# CW340_SPI_flashes.net
KiCad netlist of a schematic drawn in Altium Designer
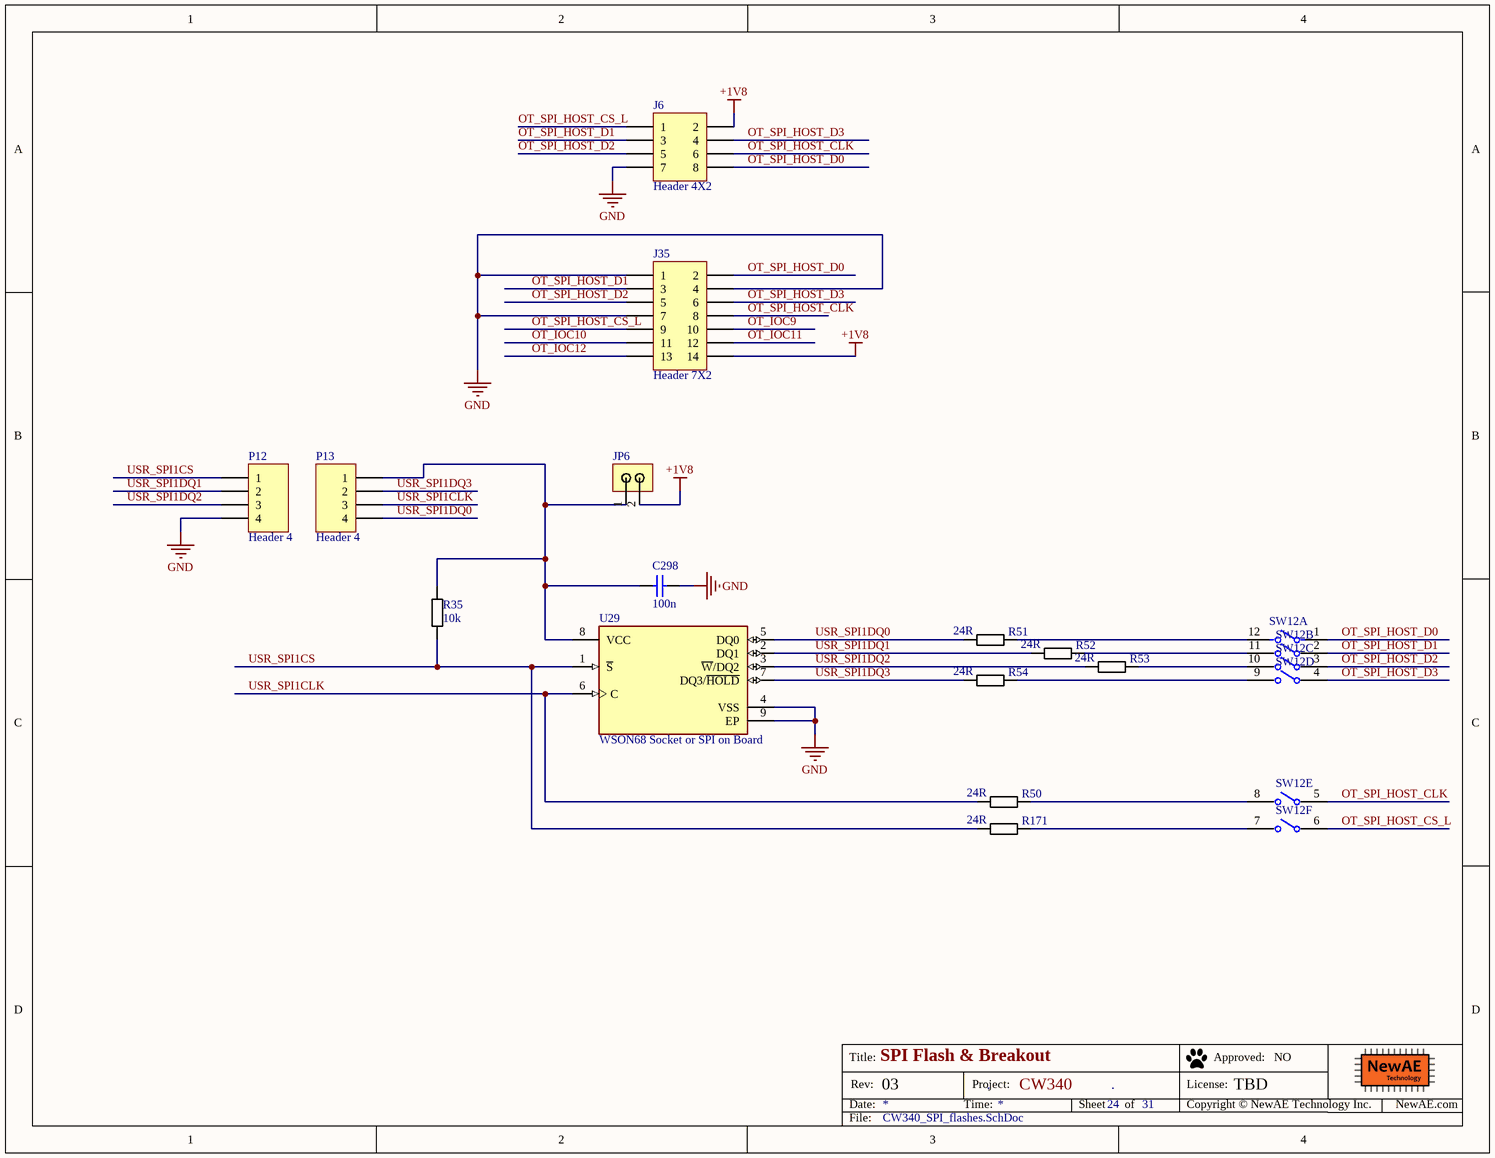
[diagram p0: CW340_SPI_flashes.SchDoc]

(export (version "E")
  (design (tool "Eeschema 10.0.6"))
  (components
    (comp (ref "C298")
      (value "100n")
      (footprint "CAPC0402_M")
      (description "100n, 0402")
      (fields (field (name "PART NUMBER") "CCHIP-100n-0402"))
      (libsource (lib "NewAE_AltiumLib") (part "CAP"))
    )
    (comp (ref "J6")
      (value "Header 4X2")
      (footprint "HDR2X4")
      (description "Header, 4-Pin, Dual row")
      (fields (field (name "PUBLISHER") "Altium Limited"))
      (libsource (lib "Miscellaneous Connectors") (part "Header 4X2"))
    )
    (comp (ref "J35")
      (value "Header 7X2")
      (footprint "HDR2X7")
      (description "Header, 7-Pin, Dual row")
      (fields (field (name "PUBLISHER") "Altium Limited"))
      (libsource (lib "Miscellaneous Connectors") (part "Header 7X2"))
    )
    (comp (ref "JP6")
      (value "Jumper")
      (footprint "2x2.54mm_Header")
      (description "1x2 2.54mm header, male pins")
      (fields (field (name "PART NUMBER") "2_PIN_JUMPER"))
      (libsource (lib "NewAE_AltiumLib") (part "1x2_Pin_Header"))
    )
    (comp (ref "P12")
      (value "Header 4")
      (footprint "HDR1X4")
      (description "Header, 4-Pin")
      (fields (field (name "PUBLISHER") "Altium Limited"))
      (libsource (lib "") (part "Header 4_1"))
    )
    (comp (ref "P13")
      (value "Header 4")
      (footprint "HDR1X4")
      (description "Header, 4-Pin")
      (fields (field (name "PUBLISHER") "Altium Limited"))
      (libsource (lib "Miscellaneous Connectors") (part "Header 4"))
    )
    (comp (ref "R35")
      (value "10k")
      (footprint "RESC1005X40N")
      (description "10k res, 0402, 1%, 1/16W")
      (fields (field (name "PART NUMBER") "RCHIP-10K-0402") (field (name "TOLERANCE") "1%"))
      (libsource (lib "NewAE_AltiumLib") (part "RES-EU"))
    )
    (comp (ref "R50")
      (value "24R")
      (footprint "RESC1005X40N")
      (description "24R res, 0402, 1%, 1/16W")
      (fields (field (name "PART NUMBER") "RCHIP-24R-0402") (field (name "TOLERANCE") "1%"))
      (libsource (lib "") (part "RES-EU_1"))
    )
    (comp (ref "R51")
      (value "24R")
      (footprint "RESC1005X40N")
      (description "24R res, 0402, 1%, 1/16W")
      (fields (field (name "PART NUMBER") "RCHIP-24R-0402") (field (name "TOLERANCE") "1%"))
      (libsource (lib "") (part "RES-EU_1"))
    )
    (comp (ref "R52")
      (value "24R")
      (footprint "RESC1005X40N")
      (description "24R res, 0402, 1%, 1/16W")
      (fields (field (name "PART NUMBER") "RCHIP-24R-0402") (field (name "TOLERANCE") "1%"))
      (libsource (lib "") (part "RES-EU_1"))
    )
    (comp (ref "R53")
      (value "24R")
      (footprint "RESC1005X40N")
      (description "24R res, 0402, 1%, 1/16W")
      (fields (field (name "PART NUMBER") "RCHIP-24R-0402") (field (name "TOLERANCE") "1%"))
      (libsource (lib "") (part "RES-EU_1"))
    )
    (comp (ref "R54")
      (value "24R")
      (footprint "RESC1005X40N")
      (description "24R res, 0402, 1%, 1/16W")
      (fields (field (name "PART NUMBER") "RCHIP-24R-0402") (field (name "TOLERANCE") "1%"))
      (libsource (lib "") (part "RES-EU_1"))
    )
    (comp (ref "R171")
      (value "24R")
      (footprint "RESC1005X40N")
      (description "24R res, 0402, 1%, 1/16W")
      (fields (field (name "PART NUMBER") "RCHIP-24R-0402") (field (name "TOLERANCE") "1%"))
      (libsource (lib "") (part "RES-EU_1"))
    )
    (comp (ref "SW12")
      (value "A6H-6101-PM")
      (footprint "FP-A6H-6101-PM-MFG")
      (description "6 DIP switch SMD")
      (libsource (lib "NewAE_AltiumLib") (part "A6H-6101-PM"))
    )
    (comp (ref "U29")
      (value "WSON68 Socket or SPI on Board")
      (footprint "SOK-SPI-WSON68_ORCHIP")
      (description "WSON-6x8 Socket OR WSON Flash")
      (fields (field (name "PART NUMBER") "SOK-SPI-WSON68_OR_QSPI"))
      (libsource (lib "NewAE_AltiumLib") (part "QSPI_WSON"))
    )
  )
  (nets
    (net (code "1") (name "+1V8") (class "Default")
      (node (ref "J35") (pin "14") (pinfunction "14_14") (pintype "passive"))
      (node (ref "J6") (pin "2") (pinfunction "2_2") (pintype "passive"))
      (node (ref "JP6") (pin "2") (pinfunction "2_2") (pintype "passive"))
    )
    (net (code "2") (name "/OT_IOC9") (class "Default")
      (node (ref "J35") (pin "10") (pinfunction "10_10") (pintype "passive"))
    )
    (net (code "3") (name "/OT_IOC10") (class "Default")
      (node (ref "J35") (pin "11") (pinfunction "11_11") (pintype "passive"))
    )
    (net (code "4") (name "/OT_IOC11") (class "Default")
      (node (ref "J35") (pin "12") (pinfunction "12_12") (pintype "passive"))
    )
    (net (code "5") (name "/OT_IOC12") (class "Default")
      (node (ref "J35") (pin "13") (pinfunction "13_13") (pintype "passive"))
    )
    (net (code "6") (name "/OT_SPI_HOST_CLK") (class "Default")
      (node (ref "J35") (pin "8") (pinfunction "8_8") (pintype "passive"))
      (node (ref "J6") (pin "6") (pinfunction "6_6") (pintype "passive"))
      (node (ref "SW12") (pin "5") (pinfunction "5_5") (pintype "passive"))
    )
    (net (code "7") (name "/OT_SPI_HOST_CS_L") (class "Default")
      (node (ref "J35") (pin "9") (pinfunction "9_9") (pintype "passive"))
      (node (ref "J6") (pin "1") (pinfunction "1_1") (pintype "passive"))
      (node (ref "SW12") (pin "6") (pinfunction "6_6") (pintype "passive"))
    )
    (net (code "8") (name "/OT_SPI_HOST_D0") (class "Default")
      (node (ref "J35") (pin "2") (pinfunction "2_2") (pintype "passive"))
      (node (ref "J6") (pin "8") (pinfunction "8_8") (pintype "passive"))
      (node (ref "SW12") (pin "1") (pinfunction "1_1") (pintype "passive"))
    )
    (net (code "9") (name "/OT_SPI_HOST_D1") (class "Default")
      (node (ref "J35") (pin "3") (pinfunction "3_3") (pintype "passive"))
      (node (ref "J6") (pin "3") (pinfunction "3_3") (pintype "passive"))
      (node (ref "SW12") (pin "2") (pinfunction "2_2") (pintype "passive"))
    )
    (net (code "10") (name "/OT_SPI_HOST_D2") (class "Default")
      (node (ref "J35") (pin "5") (pinfunction "5_5") (pintype "passive"))
      (node (ref "J6") (pin "5") (pinfunction "5_5") (pintype "passive"))
      (node (ref "SW12") (pin "3") (pinfunction "3_3") (pintype "passive"))
    )
    (net (code "11") (name "/OT_SPI_HOST_D3") (class "Default")
      (node (ref "J35") (pin "6") (pinfunction "6_6") (pintype "passive"))
      (node (ref "J6") (pin "4") (pinfunction "4_4") (pintype "passive"))
      (node (ref "SW12") (pin "4") (pinfunction "4_4") (pintype "passive"))
    )
    (net (code "12") (name "/USR_SPI1CLK") (class "Default")
      (node (ref "P13") (pin "3") (pinfunction "3_3") (pintype "passive"))
      (node (ref "R50") (pin "1") (pinfunction "1_1") (pintype "passive"))
      (node (ref "U29") (pin "6") (pinfunction "C_6") (pintype "input"))
    )
    (net (code "13") (name "/USR_SPI1CS") (class "Default")
      (node (ref "P12") (pin "1") (pinfunction "1_1") (pintype "passive"))
      (node (ref "R171") (pin "1") (pinfunction "1_1") (pintype "passive"))
      (node (ref "R35") (pin "2") (pinfunction "2_2") (pintype "passive"))
      (node (ref "U29") (pin "1") (pinfunction "~{S}_1") (pintype "input"))
    )
    (net (code "14") (name "/USR_SPI1DQ0") (class "Default")
      (node (ref "P13") (pin "4") (pinfunction "4_4") (pintype "passive"))
      (node (ref "R51") (pin "1") (pinfunction "1_1") (pintype "passive"))
      (node (ref "U29") (pin "5") (pinfunction "DQ0_5") (pintype "bidirectional"))
    )
    (net (code "15") (name "/USR_SPI1DQ1") (class "Default")
      (node (ref "P12") (pin "2") (pinfunction "2_2") (pintype "passive"))
      (node (ref "R52") (pin "1") (pinfunction "1_1") (pintype "passive"))
      (node (ref "U29") (pin "2") (pinfunction "DQ1_2") (pintype "bidirectional"))
    )
    (net (code "16") (name "/USR_SPI1DQ2") (class "Default")
      (node (ref "P12") (pin "3") (pinfunction "3_3") (pintype "passive"))
      (node (ref "R53") (pin "1") (pinfunction "1_1") (pintype "passive"))
      (node (ref "U29") (pin "3") (pinfunction "~{W}/DQ2_3") (pintype "bidirectional"))
    )
    (net (code "17") (name "/USR_SPI1DQ3") (class "Default")
      (node (ref "P13") (pin "2") (pinfunction "2_2") (pintype "passive"))
      (node (ref "R54") (pin "1") (pinfunction "1_1") (pintype "passive"))
      (node (ref "U29") (pin "7") (pinfunction "DQ3/~{HOLD}_7") (pintype "bidirectional"))
    )
    (net (code "18") (name "GND") (class "Default")
      (node (ref "C298") (pin "2") (pinfunction "2_2") (pintype "passive"))
      (node (ref "J35") (pin "1") (pinfunction "1_1") (pintype "passive"))
      (node (ref "J35") (pin "4") (pinfunction "4_4") (pintype "passive"))
      (node (ref "J35") (pin "7") (pinfunction "7_7") (pintype "passive"))
      (node (ref "J6") (pin "7") (pinfunction "7_7") (pintype "passive"))
      (node (ref "P12") (pin "4") (pinfunction "4_4") (pintype "passive"))
      (node (ref "U29") (pin "4") (pinfunction "VSS_4") (pintype "power_in"))
      (node (ref "U29") (pin "9") (pinfunction "EP_9") (pintype "power_in"))
    )
    (net (code "19") (name "Net-(R50-Pad2)") (class "Default")
      (node (ref "R50") (pin "2") (pinfunction "2_2") (pintype "passive"))
      (node (ref "SW12") (pin "8") (pinfunction "8_8") (pintype "passive"))
    )
    (net (code "20") (name "Net-(R51-Pad2)") (class "Default")
      (node (ref "R51") (pin "2") (pinfunction "2_2") (pintype "passive"))
      (node (ref "SW12") (pin "12") (pinfunction "12_12") (pintype "passive"))
    )
    (net (code "21") (name "Net-(R52-Pad2)") (class "Default")
      (node (ref "R52") (pin "2") (pinfunction "2_2") (pintype "passive"))
      (node (ref "SW12") (pin "11") (pinfunction "11_11") (pintype "passive"))
    )
    (net (code "22") (name "Net-(R53-Pad2)") (class "Default")
      (node (ref "R53") (pin "2") (pinfunction "2_2") (pintype "passive"))
      (node (ref "SW12") (pin "10") (pinfunction "10_10") (pintype "passive"))
    )
    (net (code "23") (name "Net-(R54-Pad2)") (class "Default")
      (node (ref "R54") (pin "2") (pinfunction "2_2") (pintype "passive"))
      (node (ref "SW12") (pin "9") (pinfunction "9_9") (pintype "passive"))
    )
    (net (code "24") (name "Net-(R171-Pad2)") (class "Default")
      (node (ref "R171") (pin "2") (pinfunction "2_2") (pintype "passive"))
      (node (ref "SW12") (pin "7") (pinfunction "7_7") (pintype "passive"))
    )
    (net (code "25") (name "Net-(U29-VCC)") (class "Default")
      (node (ref "C298") (pin "1") (pinfunction "1_1") (pintype "passive"))
      (node (ref "JP6") (pin "1") (pinfunction "1_1") (pintype "passive"))
      (node (ref "P13") (pin "1") (pinfunction "1_1") (pintype "passive"))
      (node (ref "R35") (pin "1") (pinfunction "1_1") (pintype "passive"))
      (node (ref "U29") (pin "8") (pinfunction "VCC_8") (pintype "power_in"))
    )
  )
)
